# H_Bridge.net
KiCad netlist of a schematic drawn in Altium Designer
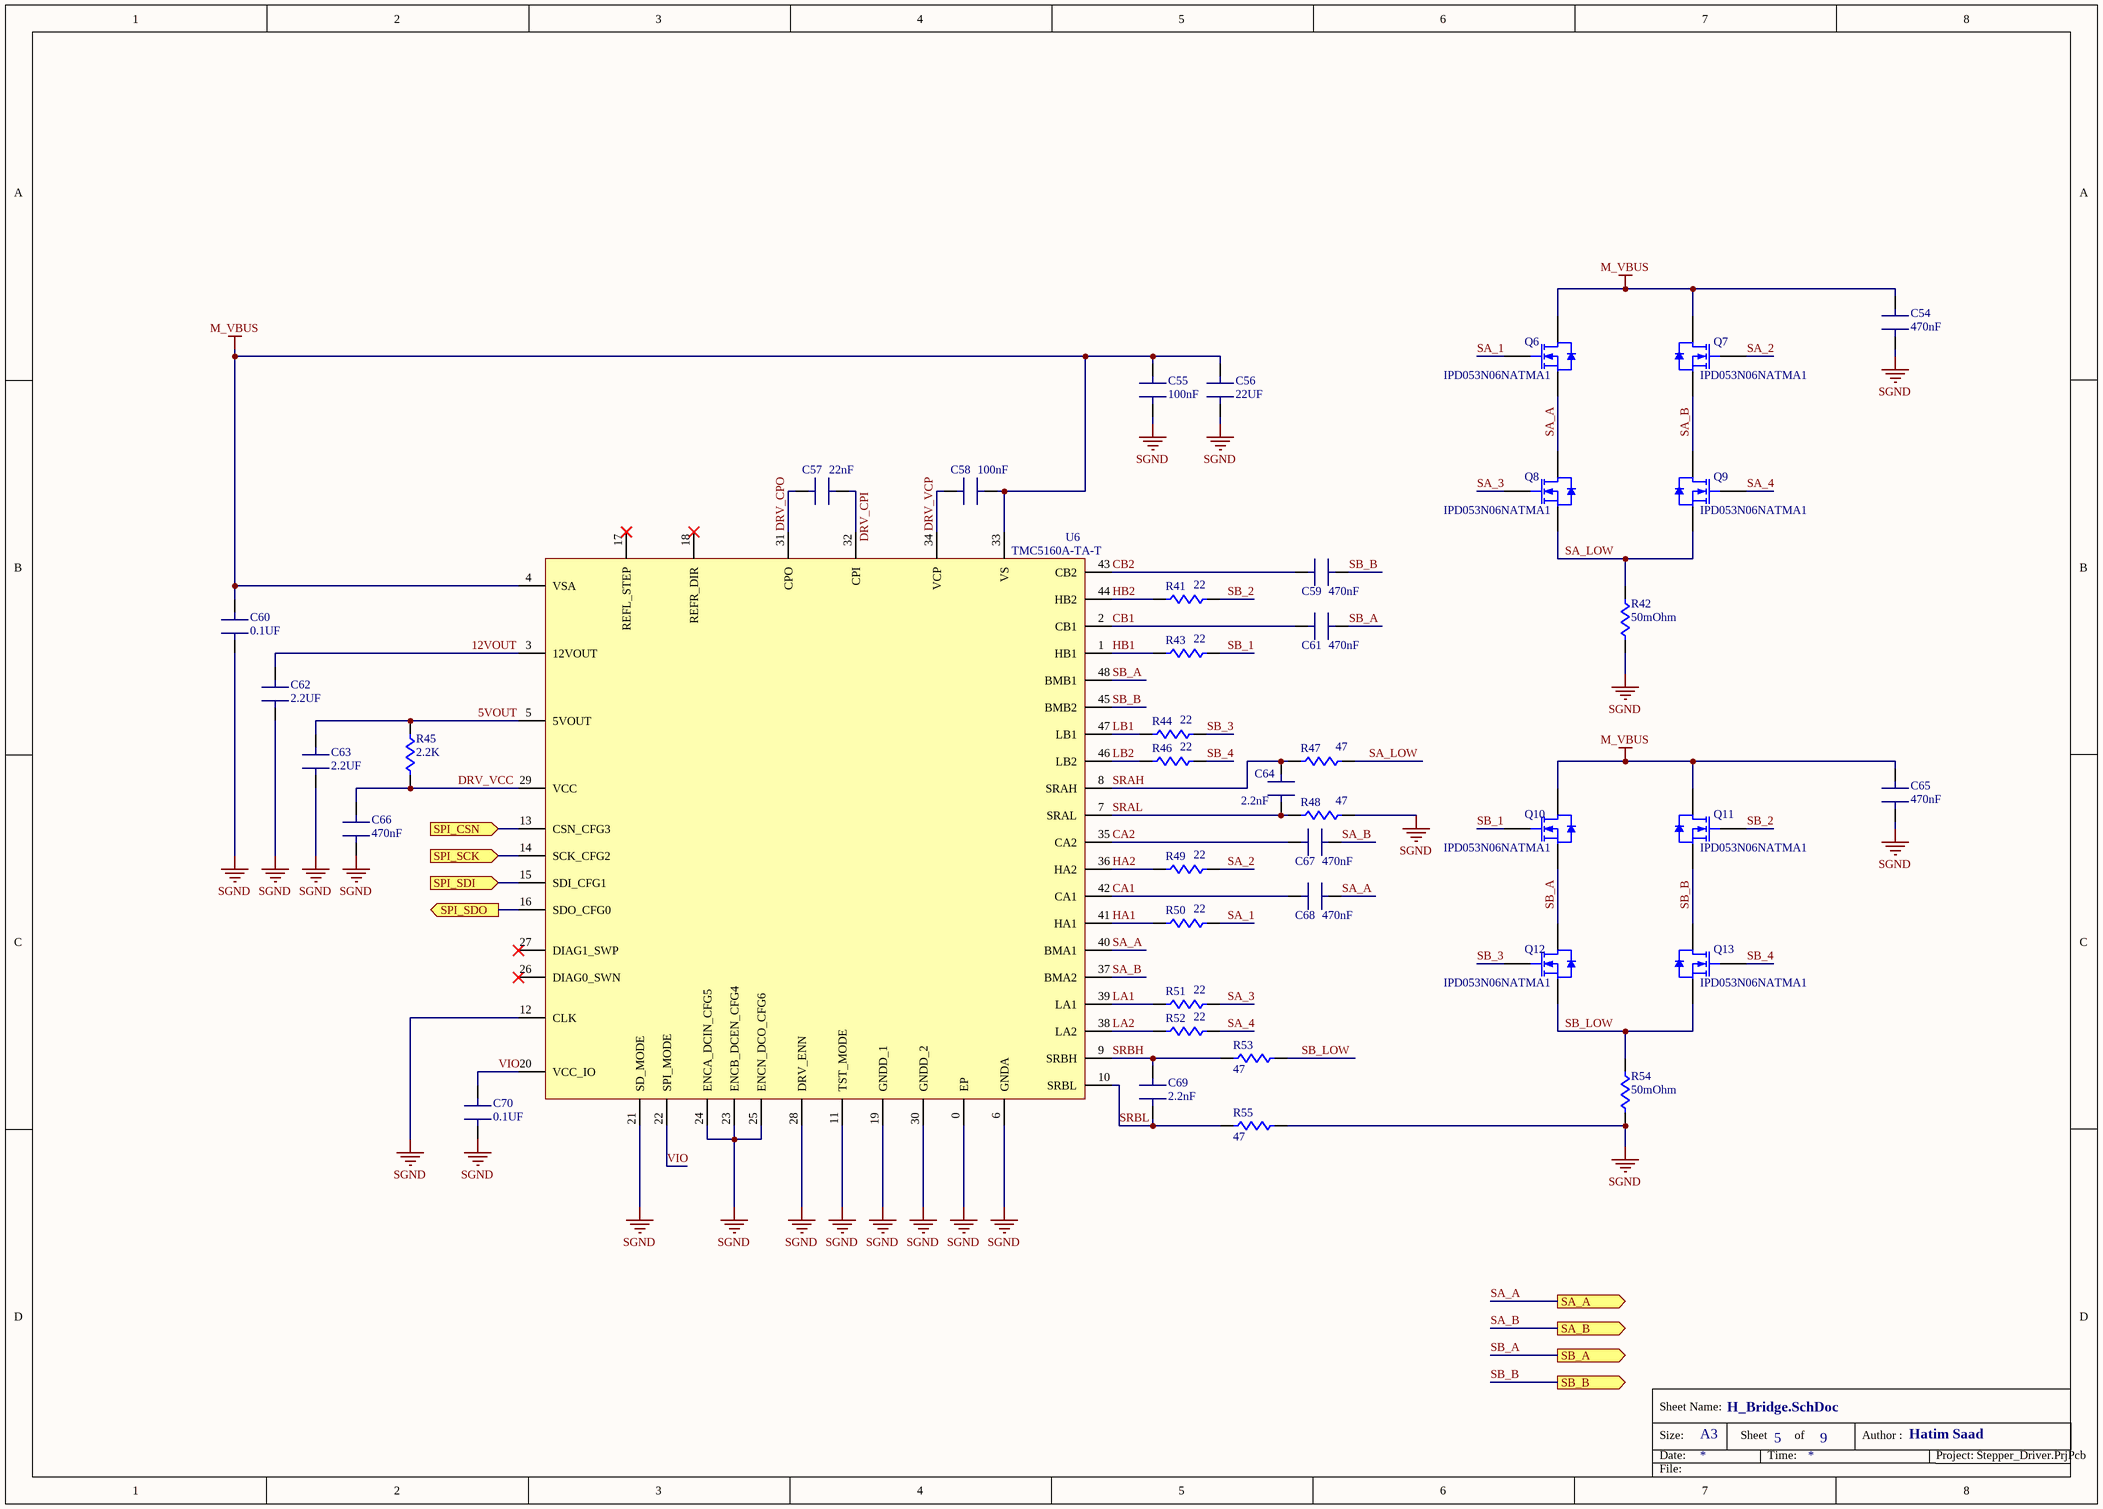
[diagram p0: H_Bridge.SchDoc]

(export (version "E")
  (design (tool "Eeschema 10.0.6"))
  (components
    (comp (ref "C54")
      (value "470nF")
      (footprint "CAP: 0805")
      (description "CAP SMD 0805")
      (libsource (lib "HZSchLib") (part "CAP 0805"))
    )
    (comp (ref "C55")
      (value "100nF")
      (footprint "CAP: 0805")
      (description "CAP SMD 0805")
      (libsource (lib "HZSchLib") (part "CAP 0805"))
    )
    (comp (ref "C56")
      (value "22UF")
      (footprint "CAP: 0805")
      (description "CAP SMD 0805")
      (libsource (lib "HZSchLib") (part "CAP 0805"))
    )
    (comp (ref "C57")
      (value "22nF")
      (footprint "CAP: 0805")
      (description "CAP SMD 0805")
      (libsource (lib "HZSchLib") (part "CAP 0805"))
    )
    (comp (ref "C58")
      (value "100nF")
      (footprint "CAP: 0805")
      (description "CAP SMD 0805")
      (libsource (lib "HZSchLib") (part "CAP 0805"))
    )
    (comp (ref "C59")
      (value "470nF")
      (footprint "CAP: 0805")
      (description "CAP SMD 0805")
      (libsource (lib "HZSchLib") (part "CAP 0805"))
    )
    (comp (ref "C60")
      (value "0.1UF")
      (footprint "CAP: 0603")
      (description "CAP SMD 0603")
      (libsource (lib "HZSchLib") (part "CAP 0603"))
    )
    (comp (ref "C61")
      (value "470nF")
      (footprint "CAP: 0805")
      (description "CAP SMD 0805")
      (libsource (lib "HZSchLib") (part "CAP 0805"))
    )
    (comp (ref "C62")
      (value "2.2UF")
      (footprint "CAP: 0603")
      (description "CAP SMD 0603")
      (libsource (lib "HZSchLib") (part "CAP 0603"))
    )
    (comp (ref "C63")
      (value "2.2UF")
      (footprint "CAP: 0603")
      (description "CAP SMD 0603")
      (libsource (lib "HZSchLib") (part "CAP 0603"))
    )
    (comp (ref "C64")
      (value "2.2nF")
      (footprint "CAP: 0603")
      (description "CAP SMD 0603")
      (libsource (lib "HZSchLib") (part "CAP 0603"))
    )
    (comp (ref "C65")
      (value "470nF")
      (footprint "CAP: 0805")
      (description "CAP SMD 0805")
      (libsource (lib "HZSchLib") (part "CAP 0805"))
    )
    (comp (ref "C66")
      (value "470nF")
      (footprint "CAP: 0603")
      (description "CAP SMD 0603")
      (libsource (lib "HZSchLib") (part "CAP 0603"))
    )
    (comp (ref "C67")
      (value "470nF")
      (footprint "CAP: 0805")
      (description "CAP SMD 0805")
      (libsource (lib "HZSchLib") (part "CAP 0805"))
    )
    (comp (ref "C68")
      (value "470nF")
      (footprint "CAP: 0805")
      (description "CAP SMD 0805")
      (libsource (lib "HZSchLib") (part "CAP 0805"))
    )
    (comp (ref "C69")
      (value "2.2nF")
      (footprint "CAP: 0603")
      (description "CAP SMD 0603")
      (libsource (lib "HZSchLib") (part "CAP 0603"))
    )
    (comp (ref "C70")
      (value "0.1UF")
      (footprint "CAP: 0603")
      (description "CAP SMD 0603")
      (libsource (lib "HZSchLib") (part "CAP 0603"))
    )
    (comp (ref "Q6")
      (value "IPD053N06NATMA1")
      (footprint "DPAK_3")
      (description "MOSFETs N-Ch 60V 45A DPAK-2")
      (libsource (lib "HZSchLib") (part "IPD053N06NATMA1"))
    )
    (comp (ref "Q7")
      (value "IPD053N06NATMA1")
      (footprint "DPAK_3")
      (description "MOSFETs N-Ch 60V 45A DPAK-2")
      (libsource (lib "HZSchLib") (part "IPD053N06NATMA1"))
    )
    (comp (ref "Q8")
      (value "IPD053N06NATMA1")
      (footprint "DPAK_3")
      (description "MOSFETs N-Ch 60V 45A DPAK-2")
      (libsource (lib "HZSchLib") (part "IPD053N06NATMA1"))
    )
    (comp (ref "Q9")
      (value "IPD053N06NATMA1")
      (footprint "DPAK_3")
      (description "MOSFETs N-Ch 60V 45A DPAK-2")
      (libsource (lib "HZSchLib") (part "IPD053N06NATMA1"))
    )
    (comp (ref "Q10")
      (value "IPD053N06NATMA1")
      (footprint "DPAK_3")
      (description "MOSFETs N-Ch 60V 45A DPAK-2")
      (libsource (lib "HZSchLib") (part "IPD053N06NATMA1"))
    )
    (comp (ref "Q11")
      (value "IPD053N06NATMA1")
      (footprint "DPAK_3")
      (description "MOSFETs N-Ch 60V 45A DPAK-2")
      (libsource (lib "HZSchLib") (part "IPD053N06NATMA1"))
    )
    (comp (ref "Q12")
      (value "IPD053N06NATMA1")
      (footprint "DPAK_3")
      (description "MOSFETs N-Ch 60V 45A DPAK-2")
      (libsource (lib "HZSchLib") (part "IPD053N06NATMA1"))
    )
    (comp (ref "Q13")
      (value "IPD053N06NATMA1")
      (footprint "DPAK_3")
      (description "MOSFETs N-Ch 60V 45A DPAK-2")
      (libsource (lib "HZSchLib") (part "IPD053N06NATMA1"))
    )
    (comp (ref "R41")
      (value "22")
      (footprint "RES: 0603")
      (description "RES SMD 0603")
      (libsource (lib "HZSchLib") (part "RES 0603"))
    )
    (comp (ref "R42")
      (value "50mOhm")
      (footprint "RES: 2512")
      (description "Current Sense Resistors - SMD TLRP 2512 2.0W R050 1% 75PPM 4K RL")
      (libsource (lib "HZSchLib") (part "TLRP3A20WR050FTE"))
    )
    (comp (ref "R43")
      (value "22")
      (footprint "RES: 0603")
      (description "RES SMD 0603")
      (libsource (lib "HZSchLib") (part "RES 0603"))
    )
    (comp (ref "R44")
      (value "22")
      (footprint "RES: 0603")
      (description "RES SMD 0603")
      (libsource (lib "HZSchLib") (part "RES 0603"))
    )
    (comp (ref "R45")
      (value "2.2K")
      (footprint "RES: 0603")
      (description "RES SMD 0603")
      (libsource (lib "HZSchLib") (part "RES 0603"))
    )
    (comp (ref "R46")
      (value "22")
      (footprint "RES: 0603")
      (description "RES SMD 0603")
      (libsource (lib "HZSchLib") (part "RES 0603"))
    )
    (comp (ref "R47")
      (value "47")
      (footprint "RES: 0603")
      (description "RES SMD 0603")
      (libsource (lib "HZSchLib") (part "RES 0603"))
    )
    (comp (ref "R48")
      (value "47")
      (footprint "RES: 0603")
      (description "RES SMD 0603")
      (libsource (lib "HZSchLib") (part "RES 0603"))
    )
    (comp (ref "R49")
      (value "22")
      (footprint "RES: 0603")
      (description "RES SMD 0603")
      (libsource (lib "HZSchLib") (part "RES 0603"))
    )
    (comp (ref "R50")
      (value "22")
      (footprint "RES: 0603")
      (description "RES SMD 0603")
      (libsource (lib "HZSchLib") (part "RES 0603"))
    )
    (comp (ref "R51")
      (value "22")
      (footprint "RES: 0603")
      (description "RES SMD 0603")
      (libsource (lib "HZSchLib") (part "RES 0603"))
    )
    (comp (ref "R52")
      (value "22")
      (footprint "RES: 0603")
      (description "RES SMD 0603")
      (libsource (lib "HZSchLib") (part "RES 0603"))
    )
    (comp (ref "R53")
      (value "47")
      (footprint "RES: 0603")
      (description "RES SMD 0603")
      (libsource (lib "HZSchLib") (part "RES 0603"))
    )
    (comp (ref "R54")
      (value "50mOhm")
      (footprint "RES: 2512")
      (description "Current Sense Resistors - SMD TLRP 2512 2.0W R050 1% 75PPM 4K RL")
      (libsource (lib "HZSchLib") (part "TLRP3A20WR050FTE"))
    )
    (comp (ref "R55")
      (value "47")
      (footprint "RES: 0603")
      (description "RES SMD 0603")
      (libsource (lib "HZSchLib") (part "RES 0603"))
    )
    (comp (ref "U6")
      (value "TMC5160A-TA-T")
      (footprint "48-TQFP")
      (libsource (lib "Stepper_DriverSCH") (part "TMC5160A-TA-T"))
    )
  )
  (nets
    (net (code "1") (name "/5VOUT") (class "Default")
      (node (ref "C63") (pin "2") (pinfunction "B_2") (pintype "passive"))
      (node (ref "R45") (pin "2") (pinfunction "2_2") (pintype "passive"))
      (node (ref "U6") (pin "5") (pinfunction "5VOUT_5") (pintype "passive"))
    )
    (net (code "2") (name "/12VOUT") (class "Default")
      (node (ref "C62") (pin "2") (pinfunction "B_2") (pintype "passive"))
      (node (ref "U6") (pin "3") (pinfunction "12VOUT_3") (pintype "passive"))
    )
    (net (code "3") (name "/CA1") (class "Default")
      (node (ref "C68") (pin "1") (pinfunction "A_1") (pintype "passive"))
      (node (ref "U6") (pin "42") (pinfunction "CA1_42") (pintype "passive"))
    )
    (net (code "4") (name "/CA2") (class "Default")
      (node (ref "C67") (pin "1") (pinfunction "A_1") (pintype "passive"))
      (node (ref "U6") (pin "35") (pinfunction "CA2_35") (pintype "passive"))
    )
    (net (code "5") (name "/CB1") (class "Default")
      (node (ref "C61") (pin "1") (pinfunction "A_1") (pintype "passive"))
      (node (ref "U6") (pin "2") (pinfunction "CB1_2") (pintype "passive"))
    )
    (net (code "6") (name "/CB2") (class "Default")
      (node (ref "C59") (pin "1") (pinfunction "A_1") (pintype "passive"))
      (node (ref "U6") (pin "43") (pinfunction "CB2_43") (pintype "passive"))
    )
    (net (code "7") (name "/DRV_CPI") (class "Default")
      (node (ref "C57") (pin "2") (pinfunction "B_2") (pintype "passive"))
      (node (ref "U6") (pin "32") (pinfunction "CPI_32") (pintype "passive"))
    )
    (net (code "8") (name "/DRV_CPO") (class "Default")
      (node (ref "C57") (pin "1") (pinfunction "A_1") (pintype "passive"))
      (node (ref "U6") (pin "31") (pinfunction "CPO_31") (pintype "passive"))
    )
    (net (code "9") (name "/DRV_VCC") (class "Default")
      (node (ref "C66") (pin "2") (pinfunction "B_2") (pintype "passive"))
      (node (ref "R45") (pin "1") (pinfunction "1_1") (pintype "passive"))
      (node (ref "U6") (pin "29") (pinfunction "VCC_29") (pintype "passive"))
    )
    (net (code "10") (name "/DRV_VCP") (class "Default")
      (node (ref "C58") (pin "1") (pinfunction "A_1") (pintype "passive"))
      (node (ref "U6") (pin "34") (pinfunction "VCP_34") (pintype "passive"))
    )
    (net (code "11") (name "/HA1") (class "Default")
      (node (ref "R50") (pin "2") (pinfunction "2_2") (pintype "passive"))
      (node (ref "U6") (pin "41") (pinfunction "HA1_41") (pintype "passive"))
    )
    (net (code "12") (name "/HA2") (class "Default")
      (node (ref "R49") (pin "2") (pinfunction "2_2") (pintype "passive"))
      (node (ref "U6") (pin "36") (pinfunction "HA2_36") (pintype "passive"))
    )
    (net (code "13") (name "/HB1") (class "Default")
      (node (ref "R43") (pin "2") (pinfunction "2_2") (pintype "passive"))
      (node (ref "U6") (pin "1") (pinfunction "HB1_1") (pintype "passive"))
    )
    (net (code "14") (name "/HB2") (class "Default")
      (node (ref "R41") (pin "2") (pinfunction "2_2") (pintype "passive"))
      (node (ref "U6") (pin "44") (pinfunction "HB2_44") (pintype "passive"))
    )
    (net (code "15") (name "/LA1") (class "Default")
      (node (ref "R51") (pin "2") (pinfunction "2_2") (pintype "passive"))
      (node (ref "U6") (pin "39") (pinfunction "LA1_39") (pintype "passive"))
    )
    (net (code "16") (name "/LA2") (class "Default")
      (node (ref "R52") (pin "2") (pinfunction "2_2") (pintype "passive"))
      (node (ref "U6") (pin "38") (pinfunction "LA2_38") (pintype "passive"))
    )
    (net (code "17") (name "/LB1") (class "Default")
      (node (ref "R44") (pin "2") (pinfunction "2_2") (pintype "passive"))
      (node (ref "U6") (pin "47") (pinfunction "LB1_47") (pintype "passive"))
    )
    (net (code "18") (name "/LB2") (class "Default")
      (node (ref "R46") (pin "2") (pinfunction "2_2") (pintype "passive"))
      (node (ref "U6") (pin "46") (pinfunction "LB2_46") (pintype "passive"))
    )
    (net (code "19") (name "/SA_1") (class "Default")
      (node (ref "Q6") (pin "1") (pinfunction "G_1") (pintype "passive"))
      (node (ref "R50") (pin "1") (pinfunction "1_1") (pintype "passive"))
    )
    (net (code "20") (name "/SA_2") (class "Default")
      (node (ref "Q7") (pin "1") (pinfunction "G_1") (pintype "passive"))
      (node (ref "R49") (pin "1") (pinfunction "1_1") (pintype "passive"))
    )
    (net (code "21") (name "/SA_3") (class "Default")
      (node (ref "Q8") (pin "1") (pinfunction "G_1") (pintype "passive"))
      (node (ref "R51") (pin "1") (pinfunction "1_1") (pintype "passive"))
    )
    (net (code "22") (name "/SA_4") (class "Default")
      (node (ref "Q9") (pin "1") (pinfunction "G_1") (pintype "passive"))
      (node (ref "R52") (pin "1") (pinfunction "1_1") (pintype "passive"))
    )
    (net (code "23") (name "/SA_A") (class "Default")
      (node (ref "C68") (pin "2") (pinfunction "B_2") (pintype "passive"))
      (node (ref "Q6") (pin "3") (pinfunction "S_3") (pintype "passive"))
      (node (ref "Q8") (pin "4") (pinfunction "D_4") (pintype "passive"))
      (node (ref "U6") (pin "40") (pinfunction "BMA1_40") (pintype "passive"))
    )
    (net (code "24") (name "/SA_B") (class "Default")
      (node (ref "C67") (pin "2") (pinfunction "B_2") (pintype "passive"))
      (node (ref "Q7") (pin "3") (pinfunction "S_3") (pintype "passive"))
      (node (ref "Q9") (pin "4") (pinfunction "D_4") (pintype "passive"))
      (node (ref "U6") (pin "37") (pinfunction "BMA2_37") (pintype "passive"))
    )
    (net (code "25") (name "/SA_LOW") (class "Default")
      (node (ref "Q8") (pin "3") (pinfunction "S_3") (pintype "passive"))
      (node (ref "Q9") (pin "3") (pinfunction "S_3") (pintype "passive"))
      (node (ref "R42") (pin "2") (pinfunction "2_2") (pintype "passive"))
      (node (ref "R47") (pin "1") (pinfunction "1_1") (pintype "passive"))
    )
    (net (code "26") (name "/SB_1") (class "Default")
      (node (ref "Q10") (pin "1") (pinfunction "G_1") (pintype "passive"))
      (node (ref "R43") (pin "1") (pinfunction "1_1") (pintype "passive"))
    )
    (net (code "27") (name "/SB_2") (class "Default")
      (node (ref "Q11") (pin "1") (pinfunction "G_1") (pintype "passive"))
      (node (ref "R41") (pin "1") (pinfunction "1_1") (pintype "passive"))
    )
    (net (code "28") (name "/SB_3") (class "Default")
      (node (ref "Q12") (pin "1") (pinfunction "G_1") (pintype "passive"))
      (node (ref "R44") (pin "1") (pinfunction "1_1") (pintype "passive"))
    )
    (net (code "29") (name "/SB_4") (class "Default")
      (node (ref "Q13") (pin "1") (pinfunction "G_1") (pintype "passive"))
      (node (ref "R46") (pin "1") (pinfunction "1_1") (pintype "passive"))
    )
    (net (code "30") (name "/SB_A") (class "Default")
      (node (ref "C61") (pin "2") (pinfunction "B_2") (pintype "passive"))
      (node (ref "Q10") (pin "3") (pinfunction "S_3") (pintype "passive"))
      (node (ref "Q12") (pin "4") (pinfunction "D_4") (pintype "passive"))
      (node (ref "U6") (pin "48") (pinfunction "BMB1_48") (pintype "passive"))
    )
    (net (code "31") (name "/SB_B") (class "Default")
      (node (ref "C59") (pin "2") (pinfunction "B_2") (pintype "passive"))
      (node (ref "Q11") (pin "3") (pinfunction "S_3") (pintype "passive"))
      (node (ref "Q13") (pin "4") (pinfunction "D_4") (pintype "passive"))
      (node (ref "U6") (pin "45") (pinfunction "BMB2_45") (pintype "passive"))
    )
    (net (code "32") (name "/SB_LOW") (class "Default")
      (node (ref "Q12") (pin "3") (pinfunction "S_3") (pintype "passive"))
      (node (ref "Q13") (pin "3") (pinfunction "S_3") (pintype "passive"))
      (node (ref "R53") (pin "1") (pinfunction "1_1") (pintype "passive"))
      (node (ref "R54") (pin "2") (pinfunction "2_2") (pintype "passive"))
    )
    (net (code "33") (name "/SPI_CSN") (class "Default")
      (node (ref "U6") (pin "13") (pinfunction "CSN_CFG3_13") (pintype "passive"))
    )
    (net (code "34") (name "/SPI_SCK") (class "Default")
      (node (ref "U6") (pin "14") (pinfunction "SCK_CFG2_14") (pintype "passive"))
    )
    (net (code "35") (name "/SPI_SDI") (class "Default")
      (node (ref "U6") (pin "15") (pinfunction "SDI_CFG1_15") (pintype "passive"))
    )
    (net (code "36") (name "/SPI_SDO") (class "Default")
      (node (ref "U6") (pin "16") (pinfunction "SDO_CFG0_16") (pintype "passive"))
    )
    (net (code "37") (name "/SRAH") (class "Default")
      (node (ref "C64") (pin "2") (pinfunction "B_2") (pintype "passive"))
      (node (ref "R47") (pin "2") (pinfunction "2_2") (pintype "passive"))
      (node (ref "U6") (pin "8") (pinfunction "SRAH_8") (pintype "passive"))
    )
    (net (code "38") (name "/SRAL") (class "Default")
      (node (ref "C64") (pin "1") (pinfunction "A_1") (pintype "passive"))
      (node (ref "R48") (pin "2") (pinfunction "2_2") (pintype "passive"))
      (node (ref "U6") (pin "7") (pinfunction "SRAL_7") (pintype "passive"))
    )
    (net (code "39") (name "/SRBH") (class "Default")
      (node (ref "C69") (pin "2") (pinfunction "B_2") (pintype "passive"))
      (node (ref "R53") (pin "2") (pinfunction "2_2") (pintype "passive"))
      (node (ref "U6") (pin "9") (pinfunction "SRBH_9") (pintype "passive"))
    )
    (net (code "40") (name "/SRBL") (class "Default")
      (node (ref "C69") (pin "1") (pinfunction "A_1") (pintype "passive"))
      (node (ref "R55") (pin "2") (pinfunction "2_2") (pintype "passive"))
      (node (ref "U6") (pin "10") (pinfunction "SRBL_10") (pintype "passive"))
    )
    (net (code "41") (name "/VIO") (class "Default")
      (node (ref "C70") (pin "2") (pinfunction "B_2") (pintype "passive"))
      (node (ref "U6") (pin "20") (pinfunction "VCC_IO_20") (pintype "passive"))
      (node (ref "U6") (pin "22") (pinfunction "SPI_MODE_22") (pintype "passive"))
    )
    (net (code "42") (name "M_VBUS") (class "Default")
      (node (ref "C54") (pin "2") (pinfunction "B_2") (pintype "passive"))
      (node (ref "C55") (pin "2") (pinfunction "B_2") (pintype "passive"))
      (node (ref "C56") (pin "1") (pinfunction "A_1") (pintype "passive"))
      (node (ref "C58") (pin "2") (pinfunction "B_2") (pintype "passive"))
      (node (ref "C60") (pin "2") (pinfunction "B_2") (pintype "passive"))
      (node (ref "C65") (pin "2") (pinfunction "B_2") (pintype "passive"))
      (node (ref "Q10") (pin "4") (pinfunction "D_4") (pintype "passive"))
      (node (ref "Q11") (pin "4") (pinfunction "D_4") (pintype "passive"))
      (node (ref "Q6") (pin "4") (pinfunction "D_4") (pintype "passive"))
      (node (ref "Q7") (pin "4") (pinfunction "D_4") (pintype "passive"))
      (node (ref "U6") (pin "33") (pinfunction "VS_33") (pintype "passive"))
      (node (ref "U6") (pin "4") (pinfunction "VSA_4") (pintype "passive"))
    )
    (net (code "43") (name "SGND") (class "Default")
      (node (ref "C54") (pin "1") (pinfunction "A_1") (pintype "passive"))
      (node (ref "C55") (pin "1") (pinfunction "A_1") (pintype "passive"))
      (node (ref "C56") (pin "2") (pinfunction "B_2") (pintype "passive"))
      (node (ref "C60") (pin "1") (pinfunction "A_1") (pintype "passive"))
      (node (ref "C62") (pin "1") (pinfunction "A_1") (pintype "passive"))
      (node (ref "C63") (pin "1") (pinfunction "A_1") (pintype "passive"))
      (node (ref "C65") (pin "1") (pinfunction "A_1") (pintype "passive"))
      (node (ref "C66") (pin "1") (pinfunction "A_1") (pintype "passive"))
      (node (ref "C70") (pin "1") (pinfunction "A_1") (pintype "passive"))
      (node (ref "R42") (pin "1") (pinfunction "1_1") (pintype "passive"))
      (node (ref "R48") (pin "1") (pinfunction "1_1") (pintype "passive"))
      (node (ref "R54") (pin "1") (pinfunction "1_1") (pintype "passive"))
      (node (ref "R55") (pin "1") (pinfunction "1_1") (pintype "passive"))
      (node (ref "U6") (pin "0") (pinfunction "EP_0") (pintype "passive"))
      (node (ref "U6") (pin "11") (pinfunction "TST_MODE_11") (pintype "passive"))
      (node (ref "U6") (pin "12") (pinfunction "CLK_12") (pintype "passive"))
      (node (ref "U6") (pin "19") (pinfunction "GNDD_1_19") (pintype "passive"))
      (node (ref "U6") (pin "21") (pinfunction "SD_MODE_21") (pintype "passive"))
      (node (ref "U6") (pin "23") (pinfunction "ENCB_DCEN_CFG4_23") (pintype "passive"))
      (node (ref "U6") (pin "24") (pinfunction "ENCA_DCIN_CFG5_24") (pintype "passive"))
      (node (ref "U6") (pin "25") (pinfunction "ENCN_DCO_CFG6_25") (pintype "passive"))
      (node (ref "U6") (pin "28") (pinfunction "DRV_ENN_28") (pintype "passive"))
      (node (ref "U6") (pin "30") (pinfunction "GNDD_2_30") (pintype "passive"))
      (node (ref "U6") (pin "6") (pinfunction "GNDA_6") (pintype "passive"))
    )
    (net (code "44") (name "unconnected-(U6-DIAG0_SWN-Pad26)") (class "Default")
      (node (ref "U6") (pin "26") (pinfunction "DIAG0_SWN_26") (pintype "passive+no_connect"))
    )
    (net (code "45") (name "unconnected-(U6-DIAG1_SWP-Pad27)") (class "Default")
      (node (ref "U6") (pin "27") (pinfunction "DIAG1_SWP_27") (pintype "passive+no_connect"))
    )
    (net (code "46") (name "unconnected-(U6-REFL_STEP-Pad17)") (class "Default")
      (node (ref "U6") (pin "17") (pinfunction "REFL_STEP_17") (pintype "passive+no_connect"))
    )
    (net (code "47") (name "unconnected-(U6-REFR_DIR-Pad18)") (class "Default")
      (node (ref "U6") (pin "18") (pinfunction "REFR_DIR_18") (pintype "passive+no_connect"))
    )
  )
)
